# HANC1_0_SCH.net
KiCad netlist of a schematic drawn in Altium Designer
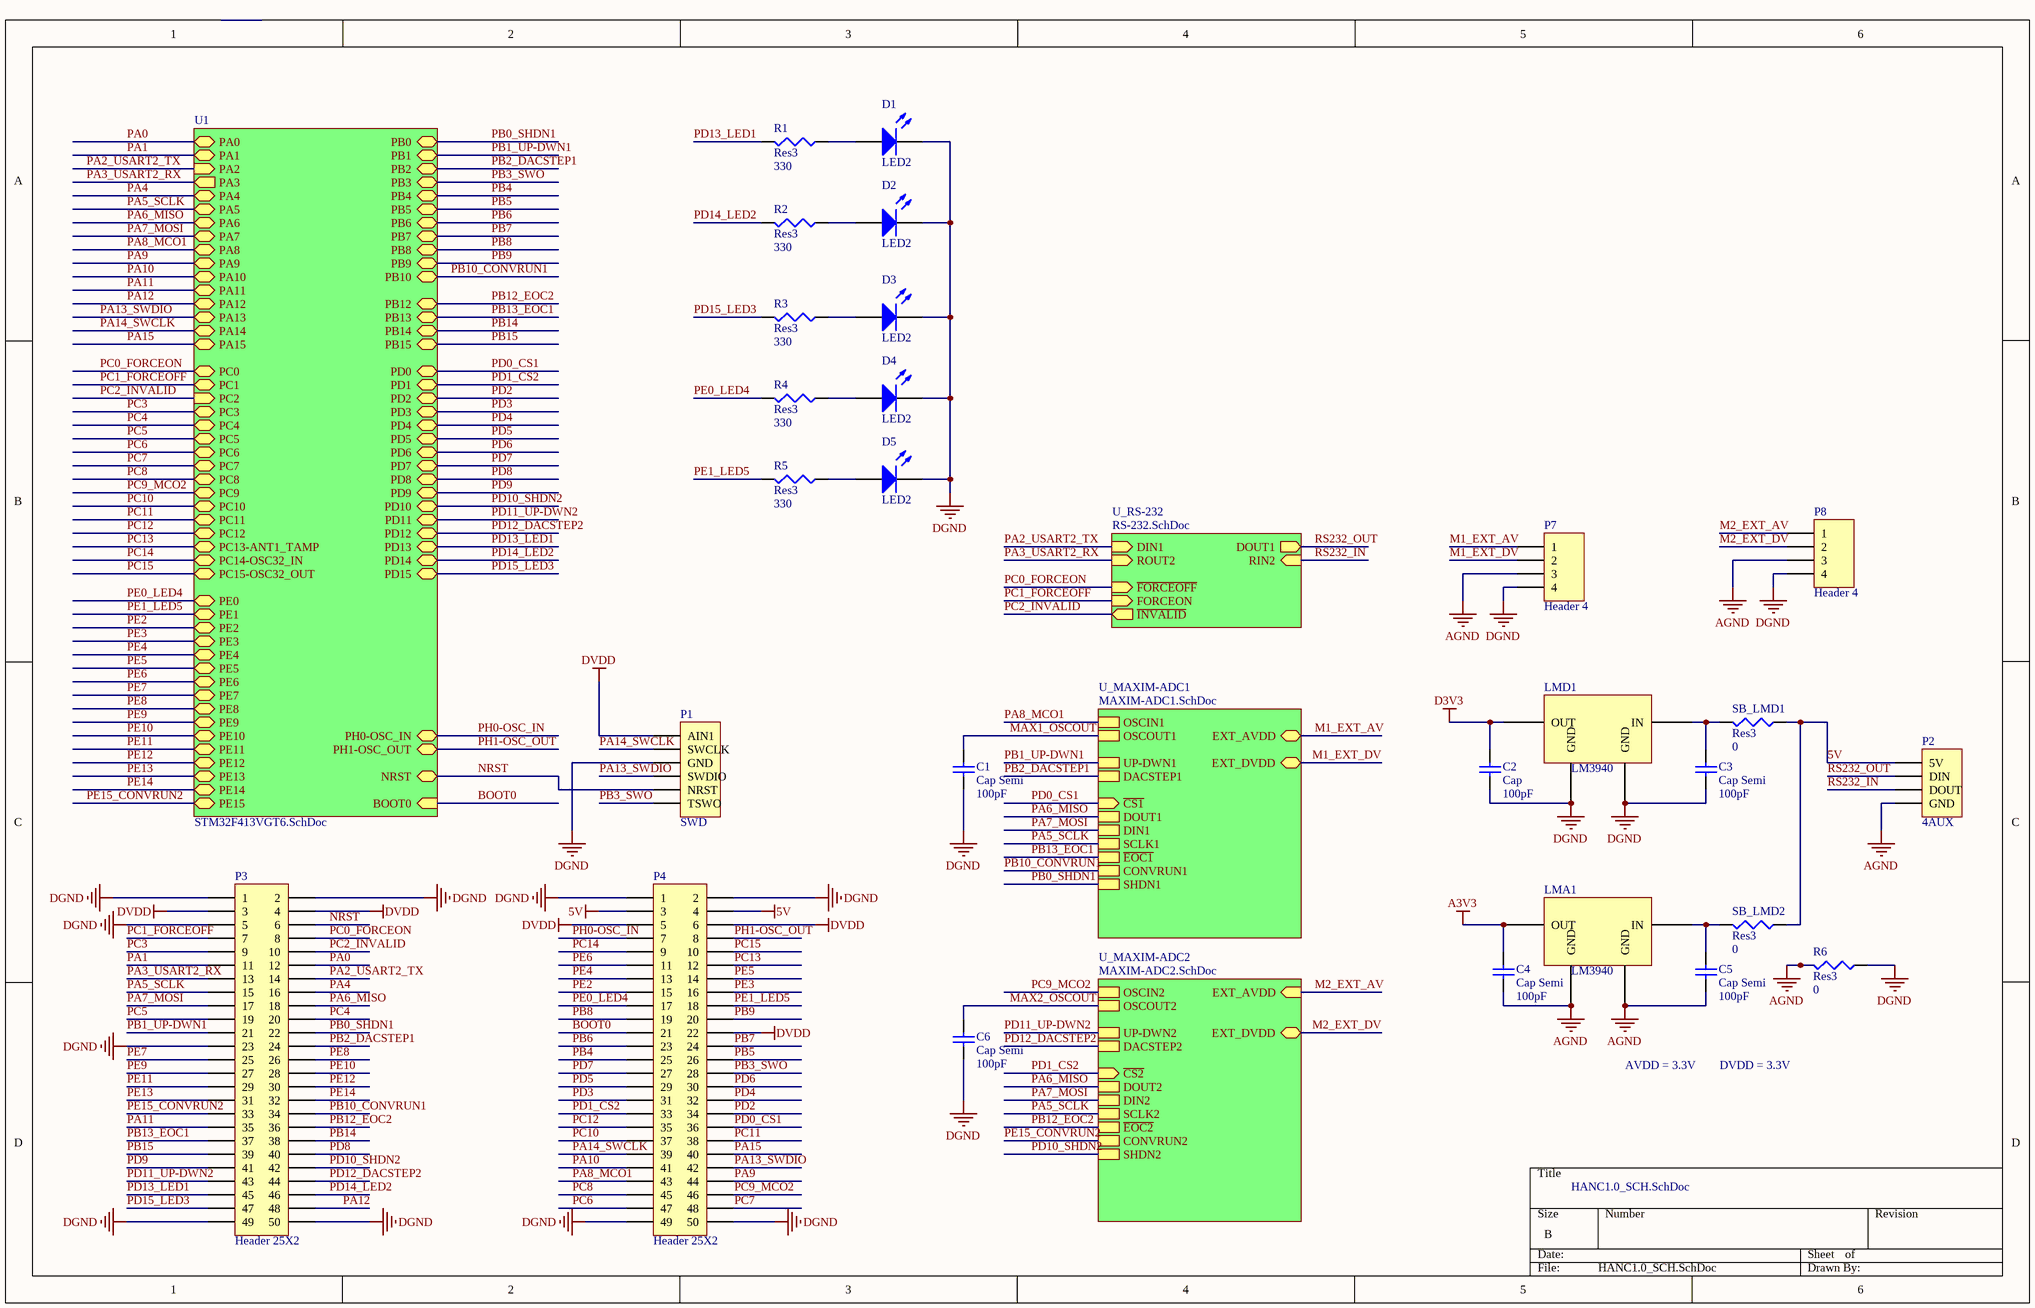
[diagram p0: HANC1.0_SCH.SchDoc]

(export (version "E")
  (design (tool "Eeschema 10.0.6"))
  (components
    (comp (ref "C1")
      (value "Cap Semi")
      (footprint "1608[0603]")
      (description "Capacitor (Semiconductor SIM Model)")
      (fields (field (name "ALTIUM_VALUE") "100pF") (field (name "PUBLISHER") "Altium Limited"))
      (libsource (lib "Miscellaneous Devices") (part "Cap Semi"))
    )
    (comp (ref "C2")
      (value "Cap")
      (footprint "1608[0603]")
      (description "Capacitor (Semiconductor SIM Model)")
      (fields (field (name "ALTIUM_VALUE") "100pF") (field (name "PUBLISHER") "Altium Limited"))
      (libsource (lib "Miscellaneous Devices") (part "Cap Semi"))
    )
    (comp (ref "C3")
      (value "Cap Semi")
      (footprint "1608[0603]")
      (description "Capacitor (Semiconductor SIM Model)")
      (fields (field (name "ALTIUM_VALUE") "100pF") (field (name "PUBLISHER") "Altium Limited"))
      (libsource (lib "Miscellaneous Devices") (part "Cap Semi"))
    )
    (comp (ref "C4")
      (value "Cap Semi")
      (footprint "1608[0603]")
      (description "Capacitor (Semiconductor SIM Model)")
      (fields (field (name "ALTIUM_VALUE") "100pF") (field (name "PUBLISHER") "Altium Limited"))
      (libsource (lib "Miscellaneous Devices") (part "Cap Semi"))
    )
    (comp (ref "C5")
      (value "Cap Semi")
      (footprint "1608[0603]")
      (description "Capacitor (Semiconductor SIM Model)")
      (fields (field (name "ALTIUM_VALUE") "100pF") (field (name "PUBLISHER") "Altium Limited"))
      (libsource (lib "Miscellaneous Devices") (part "Cap Semi"))
    )
    (comp (ref "C6")
      (value "Cap Semi")
      (footprint "1608[0603]")
      (description "Capacitor (Semiconductor SIM Model)")
      (fields (field (name "ALTIUM_VALUE") "100pF") (field (name "PUBLISHER") "Altium Limited"))
      (libsource (lib "Miscellaneous Devices") (part "Cap Semi"))
    )
    (comp (ref "D1")
      (value "LED2")
      (footprint "3.2X1.6X1.1")
      (description "Typical RED, GREEN, YELLOW, AMBER GaAs LED")
      (fields (field (name "PUBLISHER") "Altium Limited"))
      (libsource (lib "Miscellaneous Devices") (part "LED2"))
    )
    (comp (ref "D2")
      (value "LED2")
      (footprint "3.2X1.6X1.1")
      (description "Typical RED, GREEN, YELLOW, AMBER GaAs LED")
      (fields (field (name "PUBLISHER") "Altium Limited"))
      (libsource (lib "Miscellaneous Devices") (part "LED2"))
    )
    (comp (ref "D3")
      (value "LED2")
      (footprint "3.2X1.6X1.1")
      (description "Typical RED, GREEN, YELLOW, AMBER GaAs LED")
      (fields (field (name "PUBLISHER") "Altium Limited"))
      (libsource (lib "Miscellaneous Devices") (part "LED2"))
    )
    (comp (ref "D4")
      (value "LED2")
      (footprint "3.2X1.6X1.1")
      (description "Typical RED, GREEN, YELLOW, AMBER GaAs LED")
      (fields (field (name "PUBLISHER") "Altium Limited"))
      (libsource (lib "Miscellaneous Devices") (part "LED2"))
    )
    (comp (ref "D5")
      (value "LED2")
      (footprint "3.2X1.6X1.1")
      (description "Typical RED, GREEN, YELLOW, AMBER GaAs LED")
      (fields (field (name "PUBLISHER") "Altium Limited"))
      (libsource (lib "Miscellaneous Devices") (part "LED2"))
    )
    (comp (ref "LMA1")
      (value "LM3940")
      (footprint "SOT223_N")
      (libsource (lib "LN3940") (part "Component_1"))
    )
    (comp (ref "LMD1")
      (value "LM3940")
      (footprint "SOT223_N")
      (libsource (lib "LN3940") (part "Component_1"))
    )
    (comp (ref "P1")
      (value "SWD")
      (footprint "HDR1X6")
      (description "Header, 6-Pin")
      (fields (field (name "PUBLISHER") "Altium Limited"))
      (libsource (lib "Miscellaneous Connectors") (part "Header 6"))
    )
    (comp (ref "P2")
      (value "4AUX")
      (footprint "HDR1X4")
      (description "Header, 4-Pin")
      (fields (field (name "PUBLISHER") "Altium Limited"))
      (libsource (lib "Miscellaneous Connectors") (part "Header 4"))
    )
    (comp (ref "P3")
      (value "Header 25X2")
      (footprint "HDR2X25")
      (description "Header, 25-Pin, Dual row")
      (fields (field (name "PUBLISHER") "Altium Limited"))
      (libsource (lib "Miscellaneous Connectors") (part "Header 25X2"))
    )
    (comp (ref "P4")
      (value "Header 25X2")
      (footprint "HDR2X25")
      (description "Header, 25-Pin, Dual row")
      (fields (field (name "PUBLISHER") "Altium Limited"))
      (libsource (lib "Miscellaneous Connectors") (part "Header 25X2"))
    )
    (comp (ref "P7")
      (value "Header 4")
      (footprint "HDR1X4")
      (description "Header, 4-Pin")
      (fields (field (name "PUBLISHER") "Altium Limited"))
      (libsource (lib "Miscellaneous Connectors") (part "Header 4"))
    )
    (comp (ref "P8")
      (value "Header 4")
      (footprint "HDR1X4")
      (description "Header, 4-Pin")
      (fields (field (name "PUBLISHER") "Altium Limited"))
      (libsource (lib "Miscellaneous Connectors") (part "Header 4"))
    )
    (comp (ref "R1")
      (value "Res3")
      (footprint "J1-0603")
      (description "Resistor")
      (fields (field (name "ALTIUM_VALUE") "330") (field (name "PUBLISHER") "Altium Limited"))
      (libsource (lib "Miscellaneous Devices") (part "Res3"))
    )
    (comp (ref "R2")
      (value "Res3")
      (footprint "J1-0603")
      (description "Resistor")
      (fields (field (name "ALTIUM_VALUE") "330") (field (name "PUBLISHER") "Altium Limited"))
      (libsource (lib "Miscellaneous Devices") (part "Res3"))
    )
    (comp (ref "R3")
      (value "Res3")
      (footprint "J1-0603")
      (description "Resistor")
      (fields (field (name "ALTIUM_VALUE") "330") (field (name "PUBLISHER") "Altium Limited"))
      (libsource (lib "Miscellaneous Devices") (part "Res3"))
    )
    (comp (ref "R4")
      (value "Res3")
      (footprint "J1-0603")
      (description "Resistor")
      (fields (field (name "ALTIUM_VALUE") "330") (field (name "PUBLISHER") "Altium Limited"))
      (libsource (lib "Miscellaneous Devices") (part "Res3"))
    )
    (comp (ref "R5")
      (value "Res3")
      (footprint "J1-0603")
      (description "Resistor")
      (fields (field (name "ALTIUM_VALUE") "330") (field (name "PUBLISHER") "Altium Limited"))
      (libsource (lib "Miscellaneous Devices") (part "Res3"))
    )
    (comp (ref "R6")
      (value "Res3")
      (footprint "J1-0603")
      (description "Resistor")
      (fields (field (name "ALTIUM_VALUE") "0") (field (name "PUBLISHER") "Altium Limited"))
      (libsource (lib "Miscellaneous Devices") (part "Res3"))
    )
    (comp (ref "SB_LMD1")
      (value "Res3")
      (footprint "J1-0603")
      (description "Resistor")
      (fields (field (name "ALTIUM_VALUE") "0") (field (name "PUBLISHER") "Altium Limited"))
      (libsource (lib "Miscellaneous Devices") (part "Res3"))
    )
    (comp (ref "SB_LMD2")
      (value "Res3")
      (footprint "J1-0603")
      (description "Resistor")
      (fields (field (name "ALTIUM_VALUE") "0") (field (name "PUBLISHER") "Altium Limited"))
      (libsource (lib "Miscellaneous Devices") (part "Res3"))
    )
  )
  (nets
    (net (code "1") (name "/BOOT0") (class "Default")
      (node (ref "P4") (pin "21") (pinfunction "21_21") (pintype "passive"))
    )
    (net (code "2") (name "/M1_EXT_AV") (class "Default")
      (node (ref "P7") (pin "1") (pinfunction "1_1") (pintype "passive"))
    )
    (net (code "3") (name "/M1_EXT_DV") (class "Default")
      (node (ref "P7") (pin "2") (pinfunction "2_2") (pintype "passive"))
    )
    (net (code "4") (name "/M2_EXT_AV") (class "Default")
      (node (ref "P8") (pin "1") (pinfunction "1_1") (pintype "passive"))
    )
    (net (code "5") (name "/M2_EXT_DV") (class "Default")
      (node (ref "P8") (pin "2") (pinfunction "2_2") (pintype "passive"))
    )
    (net (code "6") (name "/MAX1_OSCOUT") (class "Default")
      (node (ref "C1") (pin "2") (pinfunction "2_2") (pintype "passive"))
    )
    (net (code "7") (name "/MAX2_OSCOUT") (class "Default")
      (node (ref "C6") (pin "2") (pinfunction "2_2") (pintype "passive"))
    )
    (net (code "8") (name "/NRST") (class "Default")
      (node (ref "P1") (pin "5") (pinfunction "NRST_5") (pintype "passive"))
      (node (ref "P3") (pin "6") (pinfunction "6_6") (pintype "passive"))
    )
    (net (code "9") (name "/PA0") (class "Default")
      (node (ref "P3") (pin "12") (pinfunction "12_12") (pintype "passive"))
    )
    (net (code "10") (name "/PA1") (class "Default")
      (node (ref "P3") (pin "11") (pinfunction "11_11") (pintype "passive"))
    )
    (net (code "11") (name "/PA2_USART2_TX") (class "Default")
      (node (ref "P3") (pin "14") (pinfunction "14_14") (pintype "passive"))
    )
    (net (code "12") (name "/PA3_USART2_RX") (class "Default")
      (node (ref "P3") (pin "13") (pinfunction "13_13") (pintype "passive"))
    )
    (net (code "13") (name "/PA4") (class "Default")
      (node (ref "P3") (pin "16") (pinfunction "16_16") (pintype "passive"))
    )
    (net (code "14") (name "/PA5_SCLK") (class "Default")
      (node (ref "P3") (pin "15") (pinfunction "15_15") (pintype "passive"))
    )
    (net (code "15") (name "/PA6_MISO") (class "Default")
      (node (ref "P3") (pin "18") (pinfunction "18_18") (pintype "passive"))
    )
    (net (code "16") (name "/PA7_MOSI") (class "Default")
      (node (ref "P3") (pin "17") (pinfunction "17_17") (pintype "passive"))
    )
    (net (code "17") (name "/PA8_MCO1") (class "Default")
      (node (ref "P4") (pin "43") (pinfunction "43_43") (pintype "passive"))
    )
    (net (code "18") (name "/PA9") (class "Default")
      (node (ref "P4") (pin "44") (pinfunction "44_44") (pintype "passive"))
    )
    (net (code "19") (name "/PA10") (class "Default")
      (node (ref "P4") (pin "41") (pinfunction "41_41") (pintype "passive"))
    )
    (net (code "20") (name "/PA11") (class "Default")
      (node (ref "P3") (pin "35") (pinfunction "35_35") (pintype "passive"))
    )
    (net (code "21") (name "/PA12") (class "Default")
      (node (ref "P3") (pin "48") (pinfunction "48_48") (pintype "passive"))
    )
    (net (code "22") (name "/PA13_SWDIO") (class "Default")
      (node (ref "P1") (pin "4") (pinfunction "SWDIO_4") (pintype "passive"))
      (node (ref "P4") (pin "42") (pinfunction "42_42") (pintype "passive"))
    )
    (net (code "23") (name "/PA14_SWCLK") (class "Default")
      (node (ref "P1") (pin "2") (pinfunction "SWCLK_2") (pintype "passive"))
      (node (ref "P4") (pin "39") (pinfunction "39_39") (pintype "passive"))
    )
    (net (code "24") (name "/PA15") (class "Default")
      (node (ref "P4") (pin "40") (pinfunction "40_40") (pintype "passive"))
    )
    (net (code "25") (name "/PB0_SHDN1") (class "Default")
      (node (ref "P3") (pin "22") (pinfunction "22_22") (pintype "passive"))
    )
    (net (code "26") (name "/PB1_UP-DWN1") (class "Default")
      (node (ref "P3") (pin "21") (pinfunction "21_21") (pintype "passive"))
    )
    (net (code "27") (name "/PB2_DACSTEP1") (class "Default")
      (node (ref "P3") (pin "24") (pinfunction "24_24") (pintype "passive"))
    )
    (net (code "28") (name "/PB3_SWO") (class "Default")
      (node (ref "P1") (pin "6") (pinfunction "TSWO_6") (pintype "passive"))
      (node (ref "P4") (pin "28") (pinfunction "28_28") (pintype "passive"))
    )
    (net (code "29") (name "/PB4") (class "Default")
      (node (ref "P4") (pin "25") (pinfunction "25_25") (pintype "passive"))
    )
    (net (code "30") (name "/PB5") (class "Default")
      (node (ref "P4") (pin "26") (pinfunction "26_26") (pintype "passive"))
    )
    (net (code "31") (name "/PB6") (class "Default")
      (node (ref "P4") (pin "23") (pinfunction "23_23") (pintype "passive"))
    )
    (net (code "32") (name "/PB7") (class "Default")
      (node (ref "P4") (pin "24") (pinfunction "24_24") (pintype "passive"))
    )
    (net (code "33") (name "/PB8") (class "Default")
      (node (ref "P4") (pin "19") (pinfunction "19_19") (pintype "passive"))
    )
    (net (code "34") (name "/PB9") (class "Default")
      (node (ref "P4") (pin "20") (pinfunction "20_20") (pintype "passive"))
    )
    (net (code "35") (name "/PB10_CONVRUN1") (class "Default")
      (node (ref "P3") (pin "34") (pinfunction "34_34") (pintype "passive"))
    )
    (net (code "36") (name "/PB12_EOC2") (class "Default")
      (node (ref "P3") (pin "36") (pinfunction "36_36") (pintype "passive"))
    )
    (net (code "37") (name "/PB13_EOC1") (class "Default")
      (node (ref "P3") (pin "37") (pinfunction "37_37") (pintype "passive"))
    )
    (net (code "38") (name "/PB14") (class "Default")
      (node (ref "P3") (pin "38") (pinfunction "38_38") (pintype "passive"))
    )
    (net (code "39") (name "/PB15") (class "Default")
      (node (ref "P3") (pin "39") (pinfunction "39_39") (pintype "passive"))
    )
    (net (code "40") (name "/PC0_FORCEON") (class "Default")
      (node (ref "P3") (pin "8") (pinfunction "8_8") (pintype "passive"))
    )
    (net (code "41") (name "/PC1_FORCEOFF") (class "Default")
      (node (ref "P3") (pin "7") (pinfunction "7_7") (pintype "passive"))
    )
    (net (code "42") (name "/PC2_INVALID") (class "Default")
      (node (ref "P3") (pin "10") (pinfunction "10_10") (pintype "passive"))
    )
    (net (code "43") (name "/PC3") (class "Default")
      (node (ref "P3") (pin "9") (pinfunction "9_9") (pintype "passive"))
    )
    (net (code "44") (name "/PC4") (class "Default")
      (node (ref "P3") (pin "20") (pinfunction "20_20") (pintype "passive"))
    )
    (net (code "45") (name "/PC5") (class "Default")
      (node (ref "P3") (pin "19") (pinfunction "19_19") (pintype "passive"))
    )
    (net (code "46") (name "/PC6") (class "Default")
      (node (ref "P4") (pin "47") (pinfunction "47_47") (pintype "passive"))
    )
    (net (code "47") (name "/PC7") (class "Default")
      (node (ref "P4") (pin "48") (pinfunction "48_48") (pintype "passive"))
    )
    (net (code "48") (name "/PC8") (class "Default")
      (node (ref "P4") (pin "45") (pinfunction "45_45") (pintype "passive"))
    )
    (net (code "49") (name "/PC9_MCO2") (class "Default")
      (node (ref "P4") (pin "46") (pinfunction "46_46") (pintype "passive"))
    )
    (net (code "50") (name "/PC10") (class "Default")
      (node (ref "P4") (pin "37") (pinfunction "37_37") (pintype "passive"))
    )
    (net (code "51") (name "/PC11") (class "Default")
      (node (ref "P4") (pin "38") (pinfunction "38_38") (pintype "passive"))
    )
    (net (code "52") (name "/PC12") (class "Default")
      (node (ref "P4") (pin "35") (pinfunction "35_35") (pintype "passive"))
    )
    (net (code "53") (name "/PC13") (class "Default")
      (node (ref "P4") (pin "12") (pinfunction "12_12") (pintype "passive"))
    )
    (net (code "54") (name "/PC14") (class "Default")
      (node (ref "P4") (pin "9") (pinfunction "9_9") (pintype "passive"))
    )
    (net (code "55") (name "/PC15") (class "Default")
      (node (ref "P4") (pin "10") (pinfunction "10_10") (pintype "passive"))
    )
    (net (code "56") (name "/PD0_CS1") (class "Default")
      (node (ref "P4") (pin "36") (pinfunction "36_36") (pintype "passive"))
    )
    (net (code "57") (name "/PD1_CS2") (class "Default")
      (node (ref "P4") (pin "33") (pinfunction "33_33") (pintype "passive"))
    )
    (net (code "58") (name "/PD2") (class "Default")
      (node (ref "P4") (pin "34") (pinfunction "34_34") (pintype "passive"))
    )
    (net (code "59") (name "/PD3") (class "Default")
      (node (ref "P4") (pin "31") (pinfunction "31_31") (pintype "passive"))
    )
    (net (code "60") (name "/PD4") (class "Default")
      (node (ref "P4") (pin "32") (pinfunction "32_32") (pintype "passive"))
    )
    (net (code "61") (name "/PD5") (class "Default")
      (node (ref "P4") (pin "29") (pinfunction "29_29") (pintype "passive"))
    )
    (net (code "62") (name "/PD6") (class "Default")
      (node (ref "P4") (pin "30") (pinfunction "30_30") (pintype "passive"))
    )
    (net (code "63") (name "/PD7") (class "Default")
      (node (ref "P4") (pin "27") (pinfunction "27_27") (pintype "passive"))
    )
    (net (code "64") (name "/PD8") (class "Default")
      (node (ref "P3") (pin "40") (pinfunction "40_40") (pintype "passive"))
    )
    (net (code "65") (name "/PD9") (class "Default")
      (node (ref "P3") (pin "41") (pinfunction "41_41") (pintype "passive"))
    )
    (net (code "66") (name "/PD10_SHDN2") (class "Default")
      (node (ref "P3") (pin "42") (pinfunction "42_42") (pintype "passive"))
    )
    (net (code "67") (name "/PD11_UP-DWN2") (class "Default")
      (node (ref "P3") (pin "43") (pinfunction "43_43") (pintype "passive"))
    )
    (net (code "68") (name "/PD12_DACSTEP2") (class "Default")
      (node (ref "P3") (pin "44") (pinfunction "44_44") (pintype "passive"))
    )
    (net (code "69") (name "/PD13_LED1") (class "Default")
      (node (ref "P3") (pin "45") (pinfunction "45_45") (pintype "passive"))
      (node (ref "R1") (pin "2") (pinfunction "2_2") (pintype "passive"))
    )
    (net (code "70") (name "/PD14_LED2") (class "Default")
      (node (ref "P3") (pin "46") (pinfunction "46_46") (pintype "passive"))
      (node (ref "R2") (pin "2") (pinfunction "2_2") (pintype "passive"))
    )
    (net (code "71") (name "/PD15_LED3") (class "Default")
      (node (ref "P3") (pin "47") (pinfunction "47_47") (pintype "passive"))
      (node (ref "R3") (pin "2") (pinfunction "2_2") (pintype "passive"))
    )
    (net (code "72") (name "/PE0_LED4") (class "Default")
      (node (ref "P4") (pin "17") (pinfunction "17_17") (pintype "passive"))
      (node (ref "R4") (pin "2") (pinfunction "2_2") (pintype "passive"))
    )
    (net (code "73") (name "/PE1_LED5") (class "Default")
      (node (ref "P4") (pin "18") (pinfunction "18_18") (pintype "passive"))
      (node (ref "R5") (pin "2") (pinfunction "2_2") (pintype "passive"))
    )
    (net (code "74") (name "/PE2") (class "Default")
      (node (ref "P4") (pin "15") (pinfunction "15_15") (pintype "passive"))
    )
    (net (code "75") (name "/PE3") (class "Default")
      (node (ref "P4") (pin "16") (pinfunction "16_16") (pintype "passive"))
    )
    (net (code "76") (name "/PE4") (class "Default")
      (node (ref "P4") (pin "13") (pinfunction "13_13") (pintype "passive"))
    )
    (net (code "77") (name "/PE5") (class "Default")
      (node (ref "P4") (pin "14") (pinfunction "14_14") (pintype "passive"))
    )
    (net (code "78") (name "/PE6") (class "Default")
      (node (ref "P4") (pin "11") (pinfunction "11_11") (pintype "passive"))
    )
    (net (code "79") (name "/PE7") (class "Default")
      (node (ref "P3") (pin "25") (pinfunction "25_25") (pintype "passive"))
    )
    (net (code "80") (name "/PE8") (class "Default")
      (node (ref "P3") (pin "26") (pinfunction "26_26") (pintype "passive"))
    )
    (net (code "81") (name "/PE9") (class "Default")
      (node (ref "P3") (pin "27") (pinfunction "27_27") (pintype "passive"))
    )
    (net (code "82") (name "/PE10") (class "Default")
      (node (ref "P3") (pin "28") (pinfunction "28_28") (pintype "passive"))
    )
    (net (code "83") (name "/PE11") (class "Default")
      (node (ref "P3") (pin "29") (pinfunction "29_29") (pintype "passive"))
    )
    (net (code "84") (name "/PE12") (class "Default")
      (node (ref "P3") (pin "30") (pinfunction "30_30") (pintype "passive"))
    )
    (net (code "85") (name "/PE13") (class "Default")
      (node (ref "P3") (pin "31") (pinfunction "31_31") (pintype "passive"))
    )
    (net (code "86") (name "/PE14") (class "Default")
      (node (ref "P3") (pin "32") (pinfunction "32_32") (pintype "passive"))
    )
    (net (code "87") (name "/PE15_CONVRUN2") (class "Default")
      (node (ref "P3") (pin "33") (pinfunction "33_33") (pintype "passive"))
    )
    (net (code "88") (name "/PH0-OSC_IN") (class "Default")
      (node (ref "P4") (pin "7") (pinfunction "7_7") (pintype "passive"))
    )
    (net (code "89") (name "/PH1-OSC_OUT") (class "Default")
      (node (ref "P4") (pin "8") (pinfunction "8_8") (pintype "passive"))
    )
    (net (code "90") (name "/RS232_IN") (class "Default")
      (node (ref "P2") (pin "3") (pinfunction "3_3") (pintype "passive"))
    )
    (net (code "91") (name "/RS232_OUT") (class "Default")
      (node (ref "P2") (pin "2") (pinfunction "2_2") (pintype "passive"))
    )
    (net (code "92") (name "5V") (class "Default")
      (node (ref "P2") (pin "1") (pinfunction "1_1") (pintype "passive"))
      (node (ref "P4") (pin "3") (pinfunction "3_3") (pintype "passive"))
      (node (ref "P4") (pin "4") (pinfunction "4_4") (pintype "passive"))
      (node (ref "SB_LMD1") (pin "1") (pinfunction "1_1") (pintype "passive"))
      (node (ref "SB_LMD2") (pin "1") (pinfunction "1_1") (pintype "passive"))
    )
    (net (code "93") (name "A3V3") (class "Default")
      (node (ref "C4") (pin "2") (pinfunction "2_2") (pintype "passive"))
      (node (ref "LMA1") (pin "3") (pinfunction "OUT_3") (pintype "passive"))
    )
    (net (code "94") (name "AGND") (class "Default")
      (node (ref "C4") (pin "1") (pinfunction "1_1") (pintype "passive"))
      (node (ref "C5") (pin "1") (pinfunction "1_1") (pintype "passive"))
      (node (ref "LMA1") (pin "2") (pinfunction "GND_2") (pintype "passive"))
      (node (ref "LMA1") (pin "4") (pinfunction "GND_4") (pintype "passive"))
      (node (ref "P2") (pin "4") (pinfunction "4_4") (pintype "passive"))
      (node (ref "P7") (pin "3") (pinfunction "3_3") (pintype "passive"))
      (node (ref "P8") (pin "3") (pinfunction "3_3") (pintype "passive"))
      (node (ref "R6") (pin "2") (pinfunction "2_2") (pintype "passive"))
    )
    (net (code "95") (name "D3V3") (class "Default")
      (node (ref "C2") (pin "2") (pinfunction "2_2") (pintype "passive"))
      (node (ref "LMD1") (pin "3") (pinfunction "OUT_3") (pintype "passive"))
    )
    (net (code "96") (name "DGND") (class "Default")
      (node (ref "C1") (pin "1") (pinfunction "1_1") (pintype "passive"))
      (node (ref "C2") (pin "1") (pinfunction "1_1") (pintype "passive"))
      (node (ref "C3") (pin "1") (pinfunction "1_1") (pintype "passive"))
      (node (ref "C6") (pin "1") (pinfunction "1_1") (pintype "passive"))
      (node (ref "D1") (pin "2") (pinfunction "K_2") (pintype "passive"))
      (node (ref "D2") (pin "2") (pinfunction "K_2") (pintype "passive"))
      (node (ref "D3") (pin "2") (pinfunction "K_2") (pintype "passive"))
      (node (ref "D4") (pin "2") (pinfunction "K_2") (pintype "passive"))
      (node (ref "D5") (pin "2") (pinfunction "K_2") (pintype "passive"))
      (node (ref "LMD1") (pin "2") (pinfunction "GND_2") (pintype "passive"))
      (node (ref "LMD1") (pin "4") (pinfunction "GND_4") (pintype "passive"))
      (node (ref "P1") (pin "3") (pinfunction "GND_3") (pintype "passive"))
      (node (ref "P3") (pin "1") (pinfunction "1_1") (pintype "passive"))
      (node (ref "P3") (pin "2") (pinfunction "2_2") (pintype "passive"))
      (node (ref "P3") (pin "23") (pinfunction "23_23") (pintype "passive"))
      (node (ref "P3") (pin "49") (pinfunction "49_49") (pintype "passive"))
      (node (ref "P3") (pin "5") (pinfunction "5_5") (pintype "passive"))
      (node (ref "P3") (pin "50") (pinfunction "50_50") (pintype "passive"))
      (node (ref "P4") (pin "1") (pinfunction "1_1") (pintype "passive"))
      (node (ref "P4") (pin "2") (pinfunction "2_2") (pintype "passive"))
      (node (ref "P4") (pin "49") (pinfunction "49_49") (pintype "passive"))
      (node (ref "P4") (pin "50") (pinfunction "50_50") (pintype "passive"))
      (node (ref "P7") (pin "4") (pinfunction "4_4") (pintype "passive"))
      (node (ref "P8") (pin "4") (pinfunction "4_4") (pintype "passive"))
      (node (ref "R6") (pin "1") (pinfunction "1_1") (pintype "passive"))
    )
    (net (code "97") (name "DVDD") (class "Default")
      (node (ref "P1") (pin "1") (pinfunction "AIN1_1") (pintype "passive"))
      (node (ref "P3") (pin "3") (pinfunction "3_3") (pintype "passive"))
      (node (ref "P3") (pin "4") (pinfunction "4_4") (pintype "passive"))
      (node (ref "P4") (pin "22") (pinfunction "22_22") (pintype "passive"))
      (node (ref "P4") (pin "5") (pinfunction "5_5") (pintype "passive"))
      (node (ref "P4") (pin "6") (pinfunction "6_6") (pintype "passive"))
    )
    (net (code "98") (name "Net-(D1-A)") (class "Default")
      (node (ref "D1") (pin "1") (pinfunction "A_1") (pintype "passive"))
      (node (ref "R1") (pin "1") (pinfunction "1_1") (pintype "passive"))
    )
    (net (code "99") (name "Net-(D2-A)") (class "Default")
      (node (ref "D2") (pin "1") (pinfunction "A_1") (pintype "passive"))
      (node (ref "R2") (pin "1") (pinfunction "1_1") (pintype "passive"))
    )
    (net (code "100") (name "Net-(D3-A)") (class "Default")
      (node (ref "D3") (pin "1") (pinfunction "A_1") (pintype "passive"))
      (node (ref "R3") (pin "1") (pinfunction "1_1") (pintype "passive"))
    )
    (net (code "101") (name "Net-(D4-A)") (class "Default")
      (node (ref "D4") (pin "1") (pinfunction "A_1") (pintype "passive"))
      (node (ref "R4") (pin "1") (pinfunction "1_1") (pintype "passive"))
    )
    (net (code "102") (name "Net-(D5-A)") (class "Default")
      (node (ref "D5") (pin "1") (pinfunction "A_1") (pintype "passive"))
      (node (ref "R5") (pin "1") (pinfunction "1_1") (pintype "passive"))
    )
    (net (code "103") (name "Net-(LMA1-IN)") (class "Default")
      (node (ref "C5") (pin "2") (pinfunction "2_2") (pintype "passive"))
      (node (ref "LMA1") (pin "1") (pinfunction "IN_1") (pintype "passive"))
      (node (ref "SB_LMD2") (pin "2") (pinfunction "2_2") (pintype "passive"))
    )
    (net (code "104") (name "Net-(LMD1-IN)") (class "Default")
      (node (ref "C3") (pin "2") (pinfunction "2_2") (pintype "passive"))
      (node (ref "LMD1") (pin "1") (pinfunction "IN_1") (pintype "passive"))
      (node (ref "SB_LMD1") (pin "2") (pinfunction "2_2") (pintype "passive"))
    )
  )
)
